# nerves_key3.net
KiCad netlist of a schematic drawn in EAGLE
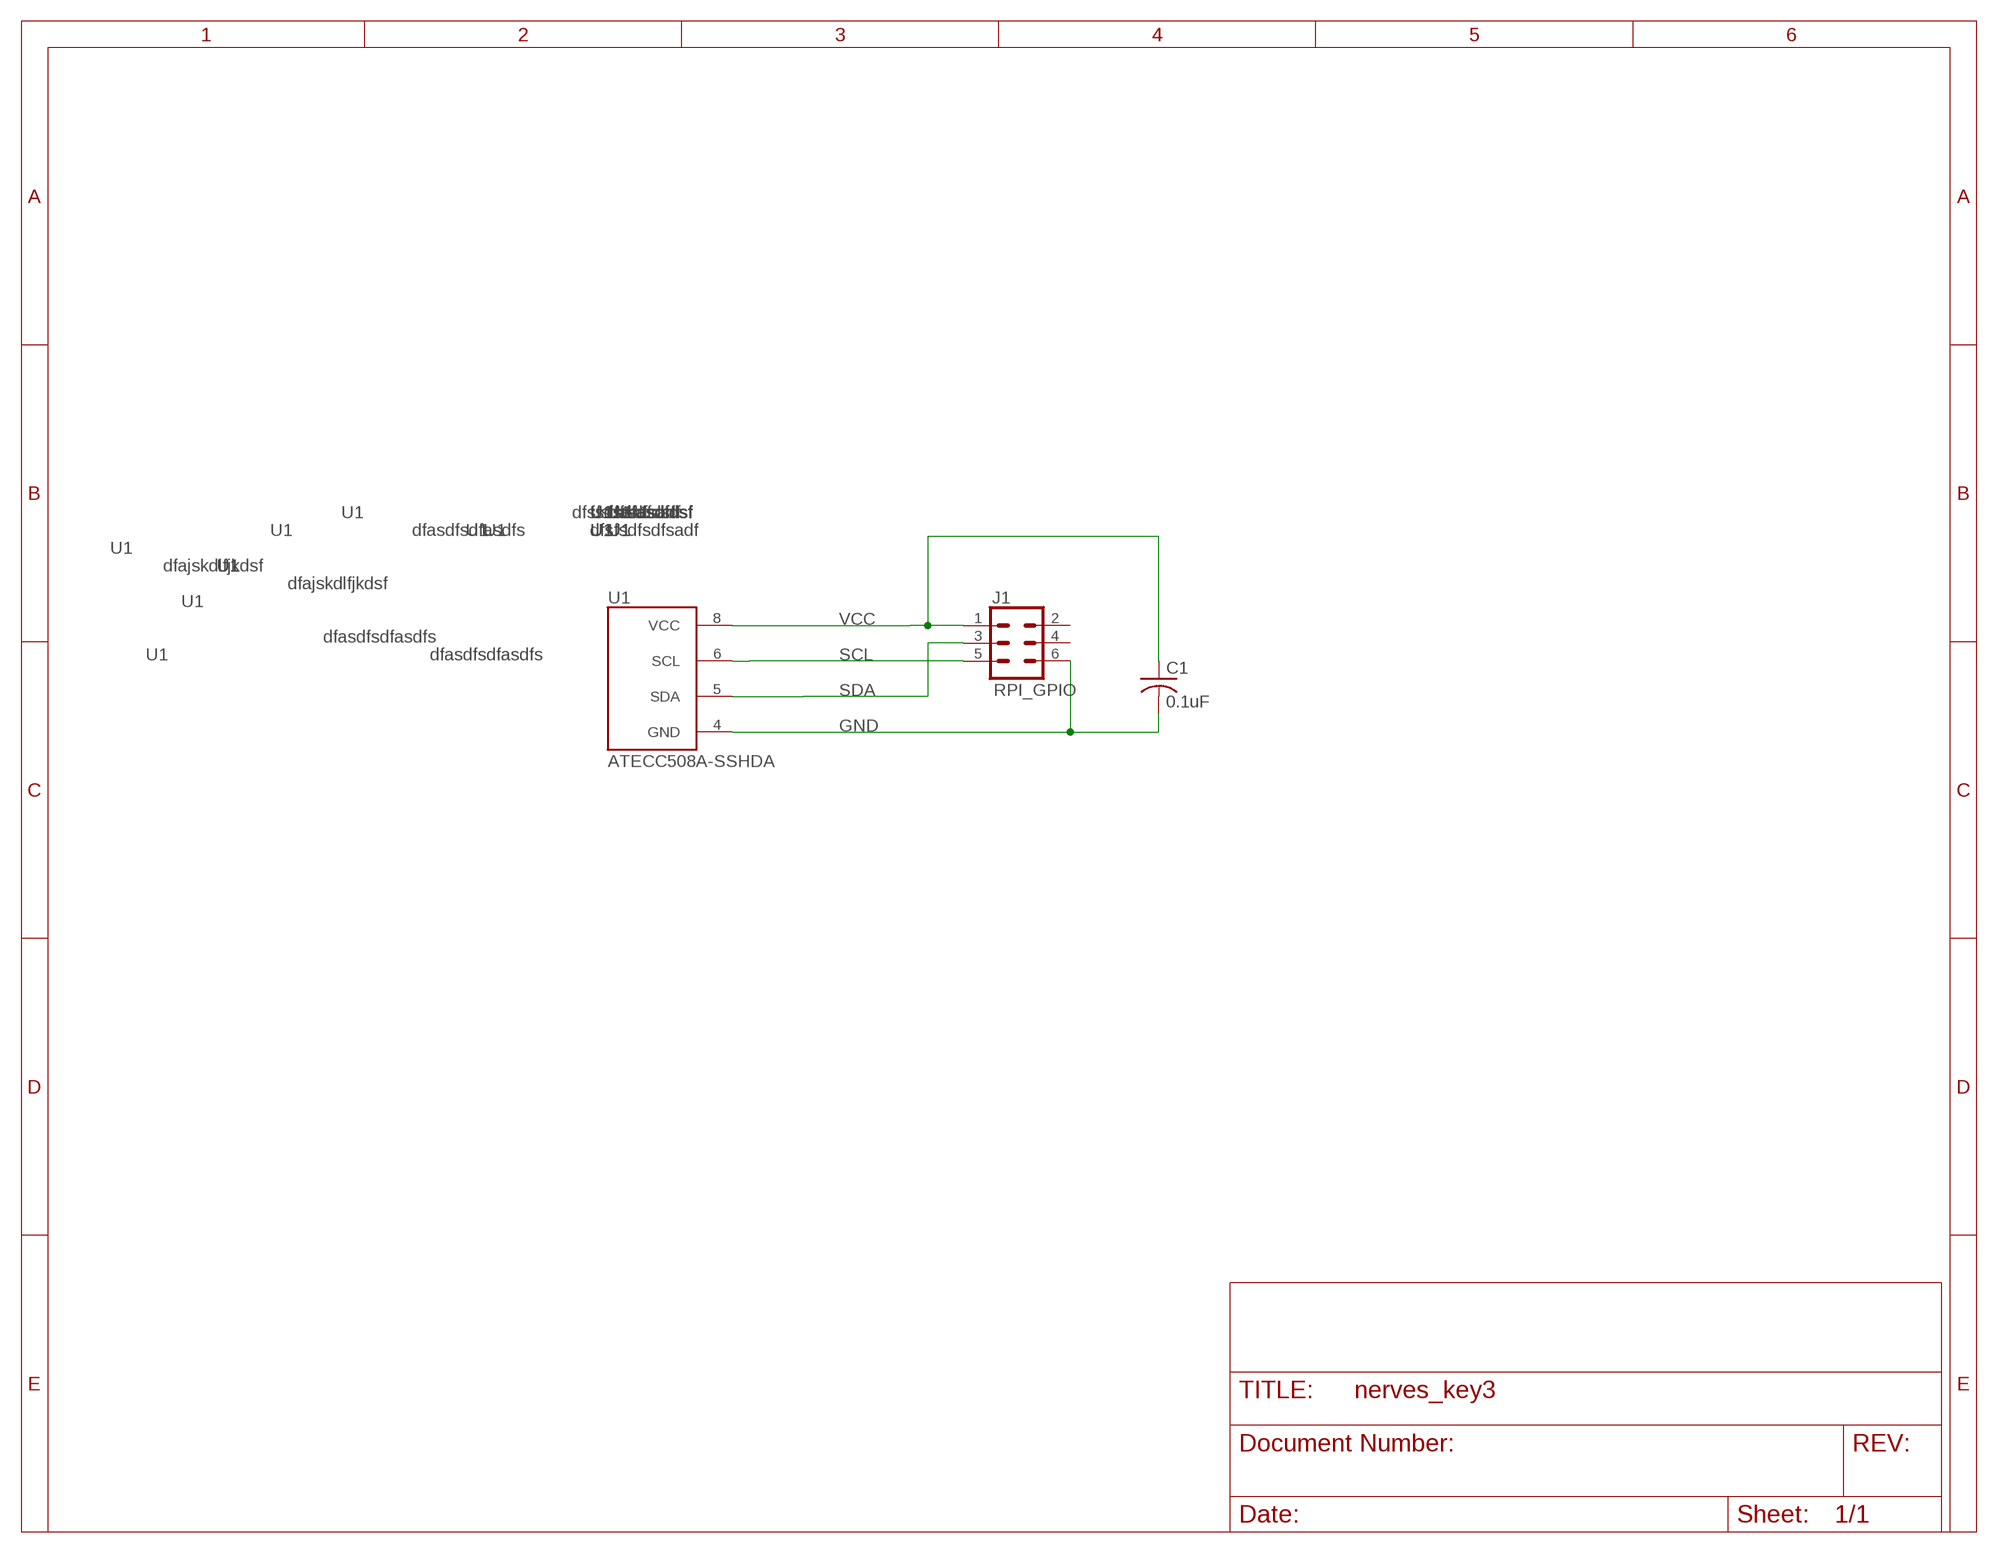
[diagram p0: schematic, sheet 1]

(export (version "E")
  (design (tool "Eeschema 10.0.6"))
  (components
    (comp (ref "C1")
      (value "0.1uF")
      (footprint "eagle-import:C0603")
      (libsource (lib "eagle-import") (part "C-USC0603"))
    )
    (comp (ref "J1")
      (value "RPI_GPIO")
      (footprint "eagle-import:2X3")
      (libsource (lib "eagle-import") (part "CONN_03X2_TIGHT"))
    )
    (comp (ref "U1")
      (value "ATECC508A-SSHDA")
      (footprint "eagle-import:SOIC127P625X175-8")
      (libsource (lib "eagle-import") (part "ATECC508ASOIC-8-NARROW"))
    )
  )
  (nets
    (net (code "1") (name "/GND") (class "Default")
      (node (ref "C1") (pin "2") (pinfunction "2_2") (pintype "passive"))
      (node (ref "J1") (pin "6") (pinfunction "6_6") (pintype "bidirectional"))
      (node (ref "U1") (pin "4") (pinfunction "GND_4") (pintype "bidirectional"))
    )
    (net (code "2") (name "/SCL") (class "Default")
      (node (ref "J1") (pin "5") (pinfunction "5_5") (pintype "bidirectional"))
      (node (ref "U1") (pin "6") (pinfunction "SCL_6") (pintype "bidirectional"))
    )
    (net (code "3") (name "/SDA") (class "Default")
      (node (ref "J1") (pin "3") (pinfunction "3_3") (pintype "bidirectional"))
      (node (ref "U1") (pin "5") (pinfunction "SDA_5") (pintype "bidirectional"))
    )
    (net (code "4") (name "/VCC") (class "Default")
      (node (ref "C1") (pin "1") (pinfunction "1_1") (pintype "passive"))
      (node (ref "J1") (pin "1") (pinfunction "1_1") (pintype "bidirectional"))
      (node (ref "U1") (pin "8") (pinfunction "VCC_8") (pintype "bidirectional"))
    )
    (net (code "5") (name "unconnected-(J1-Pad2)") (class "Default")
      (node (ref "J1") (pin "2") (pinfunction "2_2") (pintype "bidirectional"))
    )
    (net (code "6") (name "unconnected-(J1-Pad4)") (class "Default")
      (node (ref "J1") (pin "4") (pinfunction "4_4") (pintype "bidirectional"))
    )
  )
)
